# stereo_camera_v2.net
KiCad netlist of a schematic drawn in Altium Designer
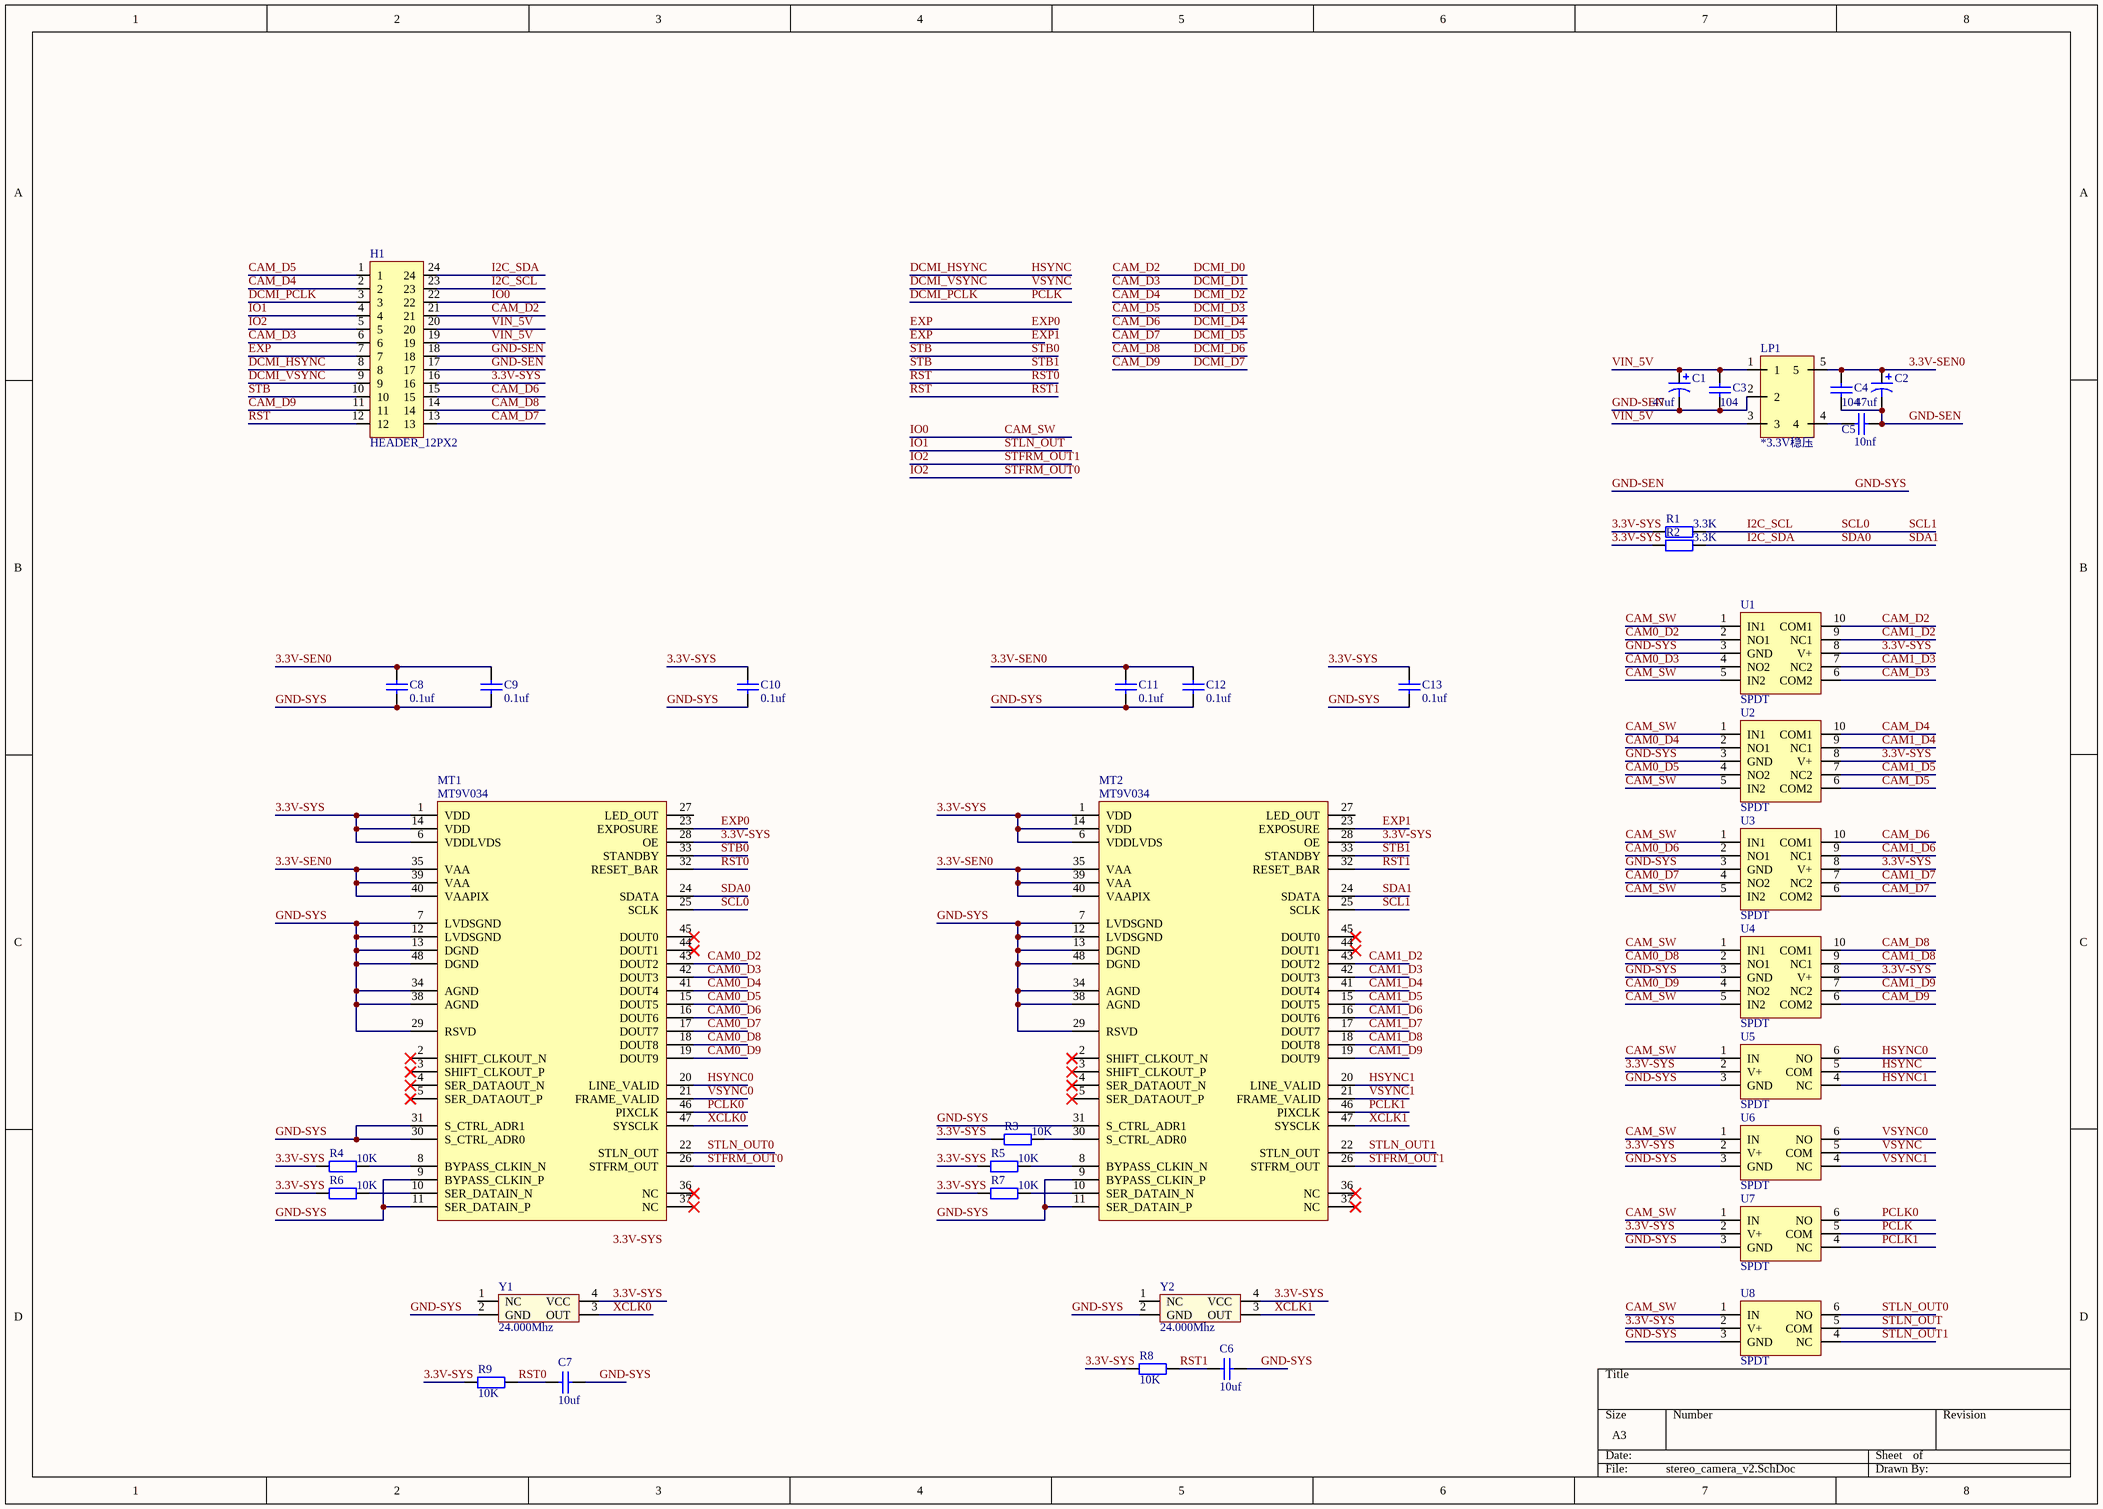
[diagram p0: stereo_camera_v2.SchDoc]

(export (version "E")
  (design (tool "Eeschema 10.0.6"))
  (components
    (comp (ref "C1") (value "47uf") (footprint "MINI-copter:3225_C") (libsource (lib "*") (part "cap_pn")))
    (comp (ref "C2") (value "47uf") (footprint "MINI-copter:3225_C") (libsource (lib "*") (part "cap_pn")))
    (comp (ref "C3")
      (value "104")
      (footprint "H3_Core:C0402")
      (description "Capacitor")
      (fields (field (name "Comment") "Cap") (field (name "PUBLISHER") "Altium Limited"))
      (libsource (lib "Miscellaneous Devices") (part "Cap"))
    )
    (comp (ref "C4")
      (value "104")
      (footprint "H3_Core:C0402")
      (description "Capacitor")
      (fields (field (name "Comment") "Cap") (field (name "PUBLISHER") "Altium Limited"))
      (libsource (lib "Miscellaneous Devices") (part "Cap"))
    )
    (comp (ref "C5")
      (value "10nf")
      (footprint "H3_Core:C0402")
      (description "Capacitor")
      (fields (field (name "Comment") "Cap") (field (name "PUBLISHER") "Altium Limited"))
      (libsource (lib "Miscellaneous Devices") (part "Cap"))
    )
    (comp (ref "C6") (value "10uf") (footprint "H3_Core:C0402") (libsource (lib "*") (part "CAP")))
    (comp (ref "C7") (value "10uf") (footprint "H3_Core:C0402") (libsource (lib "*") (part "CAP")))
    (comp (ref "C8") (value "0.1uf") (footprint "H3_Core:C0402") (libsource (lib "*") (part "CAP")))
    (comp (ref "C9") (value "0.1uf") (footprint "H3_Core:C0402") (libsource (lib "*") (part "CAP")))
    (comp (ref "C10") (value "0.1uf") (footprint "H3_Core:C0402") (libsource (lib "*") (part "CAP")))
    (comp (ref "C11") (value "0.1uf") (footprint "H3_Core:C0402") (libsource (lib "*") (part "CAP")))
    (comp (ref "C12") (value "0.1uf") (footprint "H3_Core:C0402") (libsource (lib "*") (part "CAP")))
    (comp (ref "C13") (value "0.1uf") (footprint "H3_Core:C0402") (libsource (lib "*") (part "CAP")))
    (comp (ref "H1")
      (value "HEADER_12PX2")
      (footprint "连接器:松下AXE-24PIN-0.4mm-header")
      (libsource (lib "MINI-copter") (part "HEADER_12PX2"))
    )
    (comp (ref "LP1")
      (value "*3.3V稳压")
      (footprint "MINI-copter:SOT23-5")
      (libsource (lib "Mini飞控") (part "LP2985"))
    )
    (comp (ref "MT1")
      (value "MT9V034")
      (footprint "CLCC_48")
      (description "CMOS")
      (fields (field (name "PARTNUMBER") "MT9V034C12STM-DP1"))
      (libsource (lib "Schlib1") (part "MT9V034"))
    )
    (comp (ref "MT2")
      (value "MT9V034")
      (footprint "CLCC_48")
      (description "CMOS")
      (fields (field (name "PARTNUMBER") "MT9V034C12STM-DP1"))
      (libsource (lib "Schlib1") (part "MT9V034"))
    )
    (comp (ref "R1")
      (value "3.3K")
      (footprint "H3_Core:R0402")
      (description "Resistor")
      (fields (field (name "Comment") "Res2") (field (name "PUBLISHER") "Altium Limited"))
      (libsource (lib "Miscellaneous Devices") (part "Res2"))
    )
    (comp (ref "R2")
      (value "3.3K")
      (footprint "H3_Core:R0402")
      (description "Resistor")
      (fields (field (name "Comment") "Res2") (field (name "PUBLISHER") "Altium Limited"))
      (libsource (lib "Miscellaneous Devices") (part "Res2"))
    )
    (comp (ref "R3")
      (value "10K")
      (footprint "H3_Core:R0402")
      (description "Resistor")
      (fields (field (name "Comment") "Res2") (field (name "PUBLISHER") "Altium Limited"))
      (libsource (lib "Miscellaneous Devices") (part "Res2"))
    )
    (comp (ref "R4")
      (value "10K")
      (footprint "H3_Core:R0402")
      (description "Resistor")
      (fields (field (name "Comment") "Res2") (field (name "PUBLISHER") "Altium Limited"))
      (libsource (lib "Miscellaneous Devices") (part "Res2"))
    )
    (comp (ref "R5")
      (value "10K")
      (footprint "H3_Core:R0402")
      (description "Resistor")
      (fields (field (name "Comment") "Res2") (field (name "PUBLISHER") "Altium Limited"))
      (libsource (lib "Miscellaneous Devices") (part "Res2"))
    )
    (comp (ref "R6")
      (value "10K")
      (footprint "H3_Core:R0402")
      (description "Resistor")
      (fields (field (name "Comment") "Res2") (field (name "PUBLISHER") "Altium Limited"))
      (libsource (lib "Miscellaneous Devices") (part "Res2"))
    )
    (comp (ref "R7")
      (value "10K")
      (footprint "H3_Core:R0402")
      (description "Resistor")
      (fields (field (name "Comment") "Res2") (field (name "PUBLISHER") "Altium Limited"))
      (libsource (lib "Miscellaneous Devices") (part "Res2"))
    )
    (comp (ref "R8") (value "10K") (footprint "H3_Core:R0402") (libsource (lib "*") (part "RES")))
    (comp (ref "R9") (value "10K") (footprint "H3_Core:R0402") (libsource (lib "*") (part "RES")))
    (comp (ref "U1")
      (value "SPDT")
      (footprint "MINI-copter:MSOP-10")
      (description "analog switch")
      (libsource (lib "MINI-copter") (part "sgm3002"))
    )
    (comp (ref "U2")
      (value "SPDT")
      (footprint "MINI-copter:MSOP-10")
      (description "analog switch")
      (libsource (lib "MINI-copter") (part "sgm3002"))
    )
    (comp (ref "U3")
      (value "SPDT")
      (footprint "MINI-copter:MSOP-10")
      (description "analog switch")
      (libsource (lib "MINI-copter") (part "sgm3002"))
    )
    (comp (ref "U4")
      (value "SPDT")
      (footprint "MINI-copter:MSOP-10")
      (description "analog switch")
      (libsource (lib "MINI-copter") (part "sgm3002"))
    )
    (comp (ref "U5")
      (value "SPDT")
      (footprint "MINI-copter:SC70-6")
      (description "analog switch")
      (libsource (lib "MINI-copter") (part "sgm3001"))
    )
    (comp (ref "U6")
      (value "SPDT")
      (footprint "MINI-copter:SC70-6")
      (description "analog switch")
      (libsource (lib "MINI-copter") (part "sgm3001"))
    )
    (comp (ref "U7")
      (value "SPDT")
      (footprint "MINI-copter:SC70-6")
      (description "analog switch")
      (libsource (lib "MINI-copter") (part "sgm3001"))
    )
    (comp (ref "U8")
      (value "SPDT")
      (footprint "MINI-copter:SC70-6")
      (description "analog switch")
      (libsource (lib "MINI-copter") (part "sgm3001"))
    )
    (comp (ref "Y1")
      (value "24.000Mhz")
      (footprint "MINI-copter:X3225")
      (description "有源晶振")
      (libsource (lib "ATK-2014-09-12") (part "XTAL_S"))
    )
    (comp (ref "Y2")
      (value "24.000Mhz")
      (footprint "MINI-copter:X3225")
      (description "有源晶振")
      (libsource (lib "ATK-2014-09-12") (part "XTAL_S"))
    )
  )
  (nets
    (net (code "1") (name "/3.3V-SEN0") (class "Default")
      (node (ref "C11") (pin "1") (pinfunction "1_1") (pintype "passive"))
      (node (ref "C12") (pin "1") (pinfunction "1_1") (pintype "passive"))
      (node (ref "C2") (pin "1") (pinfunction "1_1") (pintype "passive"))
      (node (ref "C4") (pin "1") (pinfunction "1_1") (pintype "passive"))
      (node (ref "C8") (pin "1") (pinfunction "1_1") (pintype "passive"))
      (node (ref "C9") (pin "1") (pinfunction "1_1") (pintype "passive"))
      (node (ref "LP1") (pin "5") (pinfunction "5_5") (pintype "passive"))
      (node (ref "MT1") (pin "35") (pinfunction "VAA_35") (pintype "passive"))
      (node (ref "MT1") (pin "39") (pinfunction "VAA_39") (pintype "passive"))
      (node (ref "MT1") (pin "40") (pinfunction "VAAPIX_40") (pintype "passive"))
      (node (ref "MT2") (pin "35") (pinfunction "VAA_35") (pintype "passive"))
      (node (ref "MT2") (pin "39") (pinfunction "VAA_39") (pintype "passive"))
      (node (ref "MT2") (pin "40") (pinfunction "VAAPIX_40") (pintype "passive"))
    )
    (net (code "2") (name "/3.3V-SYS") (class "Default")
      (node (ref "C10") (pin "1") (pinfunction "1_1") (pintype "passive"))
      (node (ref "C13") (pin "1") (pinfunction "1_1") (pintype "passive"))
      (node (ref "H1") (pin "16") (pinfunction "16_16") (pintype "passive"))
      (node (ref "MT1") (pin "1") (pinfunction "VDD_1") (pintype "passive"))
      (node (ref "MT1") (pin "14") (pinfunction "VDD_14") (pintype "passive"))
      (node (ref "MT1") (pin "28") (pinfunction "OE_28") (pintype "passive"))
      (node (ref "MT1") (pin "6") (pinfunction "VDDLVDS_6") (pintype "passive"))
      (node (ref "MT2") (pin "1") (pinfunction "VDD_1") (pintype "passive"))
      (node (ref "MT2") (pin "14") (pinfunction "VDD_14") (pintype "passive"))
      (node (ref "MT2") (pin "28") (pinfunction "OE_28") (pintype "passive"))
      (node (ref "MT2") (pin "6") (pinfunction "VDDLVDS_6") (pintype "passive"))
      (node (ref "R1") (pin "2") (pinfunction "2_2") (pintype "passive"))
      (node (ref "R2") (pin "2") (pinfunction "2_2") (pintype "passive"))
      (node (ref "R3") (pin "2") (pinfunction "2_2") (pintype "passive"))
      (node (ref "R4") (pin "2") (pinfunction "2_2") (pintype "passive"))
      (node (ref "R5") (pin "2") (pinfunction "2_2") (pintype "passive"))
      (node (ref "R6") (pin "2") (pinfunction "2_2") (pintype "passive"))
      (node (ref "R7") (pin "2") (pinfunction "2_2") (pintype "passive"))
      (node (ref "R8") (pin "1") (pinfunction "1_1") (pintype "passive"))
      (node (ref "R9") (pin "1") (pinfunction "1_1") (pintype "passive"))
      (node (ref "U1") (pin "8") (pinfunction "V+_8") (pintype "passive"))
      (node (ref "U2") (pin "8") (pinfunction "V+_8") (pintype "passive"))
      (node (ref "U3") (pin "8") (pinfunction "V+_8") (pintype "passive"))
      (node (ref "U4") (pin "8") (pinfunction "V+_8") (pintype "passive"))
      (node (ref "U5") (pin "2") (pinfunction "V+_2") (pintype "passive"))
      (node (ref "U6") (pin "2") (pinfunction "V+_2") (pintype "passive"))
      (node (ref "U7") (pin "2") (pinfunction "V+_2") (pintype "passive"))
      (node (ref "U8") (pin "2") (pinfunction "V+_2") (pintype "passive"))
      (node (ref "Y1") (pin "4") (pinfunction "VCC_4") (pintype "passive"))
      (node (ref "Y2") (pin "4") (pinfunction "VCC_4") (pintype "passive"))
    )
    (net (code "3") (name "/CAM0_D2") (class "Default")
      (node (ref "MT1") (pin "43") (pinfunction "DOUT2_43") (pintype "passive"))
      (node (ref "U1") (pin "2") (pinfunction "NO1_2") (pintype "passive"))
    )
    (net (code "4") (name "/CAM0_D3") (class "Default")
      (node (ref "MT1") (pin "42") (pinfunction "DOUT3_42") (pintype "passive"))
      (node (ref "U1") (pin "4") (pinfunction "NO2_4") (pintype "passive"))
    )
    (net (code "5") (name "/CAM0_D4") (class "Default")
      (node (ref "MT1") (pin "41") (pinfunction "DOUT4_41") (pintype "passive"))
      (node (ref "U2") (pin "2") (pinfunction "NO1_2") (pintype "passive"))
    )
    (net (code "6") (name "/CAM0_D5") (class "Default")
      (node (ref "MT1") (pin "15") (pinfunction "DOUT5_15") (pintype "passive"))
      (node (ref "U2") (pin "4") (pinfunction "NO2_4") (pintype "passive"))
    )
    (net (code "7") (name "/CAM0_D6") (class "Default")
      (node (ref "MT1") (pin "16") (pinfunction "DOUT6_16") (pintype "passive"))
      (node (ref "U3") (pin "2") (pinfunction "NO1_2") (pintype "passive"))
    )
    (net (code "8") (name "/CAM0_D7") (class "Default")
      (node (ref "MT1") (pin "17") (pinfunction "DOUT7_17") (pintype "passive"))
      (node (ref "U3") (pin "4") (pinfunction "NO2_4") (pintype "passive"))
    )
    (net (code "9") (name "/CAM0_D8") (class "Default")
      (node (ref "MT1") (pin "18") (pinfunction "DOUT8_18") (pintype "passive"))
      (node (ref "U4") (pin "2") (pinfunction "NO1_2") (pintype "passive"))
    )
    (net (code "10") (name "/CAM0_D9") (class "Default")
      (node (ref "MT1") (pin "19") (pinfunction "DOUT9_19") (pintype "passive"))
      (node (ref "U4") (pin "4") (pinfunction "NO2_4") (pintype "passive"))
    )
    (net (code "11") (name "/CAM1_D2") (class "Default")
      (node (ref "MT2") (pin "43") (pinfunction "DOUT2_43") (pintype "passive"))
      (node (ref "U1") (pin "9") (pinfunction "NC1_9") (pintype "passive"))
    )
    (net (code "12") (name "/CAM1_D3") (class "Default")
      (node (ref "MT2") (pin "42") (pinfunction "DOUT3_42") (pintype "passive"))
      (node (ref "U1") (pin "7") (pinfunction "NC2_7") (pintype "passive"))
    )
    (net (code "13") (name "/CAM1_D4") (class "Default")
      (node (ref "MT2") (pin "41") (pinfunction "DOUT4_41") (pintype "passive"))
      (node (ref "U2") (pin "9") (pinfunction "NC1_9") (pintype "passive"))
    )
    (net (code "14") (name "/CAM1_D5") (class "Default")
      (node (ref "MT2") (pin "15") (pinfunction "DOUT5_15") (pintype "passive"))
      (node (ref "U2") (pin "7") (pinfunction "NC2_7") (pintype "passive"))
    )
    (net (code "15") (name "/CAM1_D6") (class "Default")
      (node (ref "MT2") (pin "16") (pinfunction "DOUT6_16") (pintype "passive"))
      (node (ref "U3") (pin "9") (pinfunction "NC1_9") (pintype "passive"))
    )
    (net (code "16") (name "/CAM1_D7") (class "Default")
      (node (ref "MT2") (pin "17") (pinfunction "DOUT7_17") (pintype "passive"))
      (node (ref "U3") (pin "7") (pinfunction "NC2_7") (pintype "passive"))
    )
    (net (code "17") (name "/CAM1_D8") (class "Default")
      (node (ref "MT2") (pin "18") (pinfunction "DOUT8_18") (pintype "passive"))
      (node (ref "U4") (pin "9") (pinfunction "NC1_9") (pintype "passive"))
    )
    (net (code "18") (name "/CAM1_D9") (class "Default")
      (node (ref "MT2") (pin "19") (pinfunction "DOUT9_19") (pintype "passive"))
      (node (ref "U4") (pin "7") (pinfunction "NC2_7") (pintype "passive"))
    )
    (net (code "19") (name "/CAM_D2") (class "Default")
      (node (ref "H1") (pin "21") (pinfunction "21_21") (pintype "passive"))
      (node (ref "U1") (pin "10") (pinfunction "COM1_10") (pintype "passive"))
    )
    (net (code "20") (name "/CAM_D3") (class "Default")
      (node (ref "H1") (pin "6") (pinfunction "6_6") (pintype "passive"))
      (node (ref "U1") (pin "6") (pinfunction "COM2_6") (pintype "passive"))
    )
    (net (code "21") (name "/CAM_D4") (class "Default")
      (node (ref "H1") (pin "2") (pinfunction "2_2") (pintype "passive"))
      (node (ref "U2") (pin "10") (pinfunction "COM1_10") (pintype "passive"))
    )
    (net (code "22") (name "/CAM_D5") (class "Default")
      (node (ref "H1") (pin "1") (pinfunction "1_1") (pintype "passive"))
      (node (ref "U2") (pin "6") (pinfunction "COM2_6") (pintype "passive"))
    )
    (net (code "23") (name "/CAM_D6") (class "Default")
      (node (ref "H1") (pin "15") (pinfunction "15_15") (pintype "passive"))
      (node (ref "U3") (pin "10") (pinfunction "COM1_10") (pintype "passive"))
    )
    (net (code "24") (name "/CAM_D7") (class "Default")
      (node (ref "H1") (pin "13") (pinfunction "13_13") (pintype "passive"))
      (node (ref "U3") (pin "6") (pinfunction "COM2_6") (pintype "passive"))
    )
    (net (code "25") (name "/CAM_D8") (class "Default")
      (node (ref "H1") (pin "14") (pinfunction "14_14") (pintype "passive"))
      (node (ref "U4") (pin "10") (pinfunction "COM1_10") (pintype "passive"))
    )
    (net (code "26") (name "/CAM_D9") (class "Default")
      (node (ref "H1") (pin "11") (pinfunction "11_11") (pintype "passive"))
      (node (ref "U4") (pin "6") (pinfunction "COM2_6") (pintype "passive"))
    )
    (net (code "27") (name "/CAM_SW") (class "Default")
      (node (ref "H1") (pin "22") (pinfunction "22_22") (pintype "passive"))
      (node (ref "U1") (pin "1") (pinfunction "IN1_1") (pintype "passive"))
      (node (ref "U1") (pin "5") (pinfunction "IN2_5") (pintype "passive"))
      (node (ref "U2") (pin "1") (pinfunction "IN1_1") (pintype "passive"))
      (node (ref "U2") (pin "5") (pinfunction "IN2_5") (pintype "passive"))
      (node (ref "U3") (pin "1") (pinfunction "IN1_1") (pintype "passive"))
      (node (ref "U3") (pin "5") (pinfunction "IN2_5") (pintype "passive"))
      (node (ref "U4") (pin "1") (pinfunction "IN1_1") (pintype "passive"))
      (node (ref "U4") (pin "5") (pinfunction "IN2_5") (pintype "passive"))
      (node (ref "U5") (pin "1") (pinfunction "IN_1") (pintype "passive"))
      (node (ref "U6") (pin "1") (pinfunction "IN_1") (pintype "passive"))
      (node (ref "U7") (pin "1") (pinfunction "IN_1") (pintype "passive"))
      (node (ref "U8") (pin "1") (pinfunction "IN_1") (pintype "passive"))
    )
    (net (code "28") (name "/DCMI_HSYNC") (class "Default")
      (node (ref "H1") (pin "8") (pinfunction "8_8") (pintype "passive"))
      (node (ref "U5") (pin "5") (pinfunction "COM_5") (pintype "passive"))
    )
    (net (code "29") (name "/DCMI_PCLK") (class "Default")
      (node (ref "H1") (pin "3") (pinfunction "3_3") (pintype "passive"))
      (node (ref "U7") (pin "5") (pinfunction "COM_5") (pintype "passive"))
    )
    (net (code "30") (name "/DCMI_VSYNC") (class "Default")
      (node (ref "H1") (pin "9") (pinfunction "9_9") (pintype "passive"))
      (node (ref "U6") (pin "5") (pinfunction "COM_5") (pintype "passive"))
    )
    (net (code "31") (name "/EXP") (class "Default")
      (node (ref "H1") (pin "7") (pinfunction "7_7") (pintype "passive"))
      (node (ref "MT1") (pin "23") (pinfunction "EXPOSURE_23") (pintype "passive"))
      (node (ref "MT2") (pin "23") (pinfunction "EXPOSURE_23") (pintype "passive"))
    )
    (net (code "32") (name "/GND-SEN") (class "Default")
      (node (ref "C1") (pin "2") (pinfunction "2_2") (pintype "passive"))
      (node (ref "C10") (pin "2") (pinfunction "2_2") (pintype "passive"))
      (node (ref "C11") (pin "2") (pinfunction "2_2") (pintype "passive"))
      (node (ref "C12") (pin "2") (pinfunction "2_2") (pintype "passive"))
      (node (ref "C13") (pin "2") (pinfunction "2_2") (pintype "passive"))
      (node (ref "C2") (pin "2") (pinfunction "2_2") (pintype "passive"))
      (node (ref "C3") (pin "1") (pinfunction "1_1") (pintype "passive"))
      (node (ref "C4") (pin "2") (pinfunction "2_2") (pintype "passive"))
      (node (ref "C5") (pin "1") (pinfunction "1_1") (pintype "passive"))
      (node (ref "C6") (pin "1") (pinfunction "1_1") (pintype "passive"))
      (node (ref "C7") (pin "2") (pinfunction "2_2") (pintype "passive"))
      (node (ref "C8") (pin "2") (pinfunction "2_2") (pintype "passive"))
      (node (ref "C9") (pin "2") (pinfunction "2_2") (pintype "passive"))
      (node (ref "H1") (pin "17") (pinfunction "17_17") (pintype "passive"))
      (node (ref "H1") (pin "18") (pinfunction "18_18") (pintype "passive"))
      (node (ref "LP1") (pin "2") (pinfunction "2_2") (pintype "passive"))
      (node (ref "MT1") (pin "11") (pinfunction "SER_DATAIN_P_11") (pintype "passive"))
      (node (ref "MT1") (pin "12") (pinfunction "LVDSGND_12") (pintype "passive"))
      (node (ref "MT1") (pin "13") (pinfunction "DGND_13") (pintype "passive"))
      (node (ref "MT1") (pin "29") (pinfunction "RSVD_29") (pintype "passive"))
      (node (ref "MT1") (pin "30") (pinfunction "S_CTRL_ADR0_30") (pintype "passive"))
      (node (ref "MT1") (pin "31") (pinfunction "S_CTRL_ADR1_31") (pintype "passive"))
      (node (ref "MT1") (pin "34") (pinfunction "AGND_34") (pintype "passive"))
      (node (ref "MT1") (pin "38") (pinfunction "AGND_38") (pintype "passive"))
      (node (ref "MT1") (pin "48") (pinfunction "DGND_48") (pintype "passive"))
      (node (ref "MT1") (pin "7") (pinfunction "LVDSGND_7") (pintype "passive"))
      (node (ref "MT1") (pin "9") (pinfunction "BYPASS_CLKIN_P_9") (pintype "passive"))
      (node (ref "MT2") (pin "11") (pinfunction "SER_DATAIN_P_11") (pintype "passive"))
      (node (ref "MT2") (pin "12") (pinfunction "LVDSGND_12") (pintype "passive"))
      (node (ref "MT2") (pin "13") (pinfunction "DGND_13") (pintype "passive"))
      (node (ref "MT2") (pin "29") (pinfunction "RSVD_29") (pintype "passive"))
      (node (ref "MT2") (pin "31") (pinfunction "S_CTRL_ADR1_31") (pintype "passive"))
      (node (ref "MT2") (pin "34") (pinfunction "AGND_34") (pintype "passive"))
      (node (ref "MT2") (pin "38") (pinfunction "AGND_38") (pintype "passive"))
      (node (ref "MT2") (pin "48") (pinfunction "DGND_48") (pintype "passive"))
      (node (ref "MT2") (pin "7") (pinfunction "LVDSGND_7") (pintype "passive"))
      (node (ref "MT2") (pin "9") (pinfunction "BYPASS_CLKIN_P_9") (pintype "passive"))
      (node (ref "U1") (pin "3") (pinfunction "GND_3") (pintype "passive"))
      (node (ref "U2") (pin "3") (pinfunction "GND_3") (pintype "passive"))
      (node (ref "U3") (pin "3") (pinfunction "GND_3") (pintype "passive"))
      (node (ref "U4") (pin "3") (pinfunction "GND_3") (pintype "passive"))
      (node (ref "U5") (pin "3") (pinfunction "GND_3") (pintype "passive"))
      (node (ref "U6") (pin "3") (pinfunction "GND_3") (pintype "passive"))
      (node (ref "U7") (pin "3") (pinfunction "GND_3") (pintype "passive"))
      (node (ref "U8") (pin "3") (pinfunction "GND_3") (pintype "passive"))
      (node (ref "Y1") (pin "2") (pinfunction "GND_2") (pintype "passive"))
      (node (ref "Y2") (pin "2") (pinfunction "GND_2") (pintype "passive"))
    )
    (net (code "33") (name "/HSYNC0") (class "Default")
      (node (ref "MT1") (pin "20") (pinfunction "LINE_VALID_20") (pintype "passive"))
      (node (ref "U5") (pin "6") (pinfunction "NO_6") (pintype "passive"))
    )
    (net (code "34") (name "/HSYNC1") (class "Default")
      (node (ref "MT2") (pin "20") (pinfunction "LINE_VALID_20") (pintype "passive"))
      (node (ref "U5") (pin "4") (pinfunction "NC_4") (pintype "passive"))
    )
    (net (code "35") (name "/I2C_SCL") (class "Default")
      (node (ref "H1") (pin "23") (pinfunction "23_23") (pintype "passive"))
      (node (ref "MT1") (pin "25") (pinfunction "SCLK_25") (pintype "passive"))
      (node (ref "MT2") (pin "25") (pinfunction "SCLK_25") (pintype "passive"))
      (node (ref "R1") (pin "1") (pinfunction "1_1") (pintype "passive"))
    )
    (net (code "36") (name "/I2C_SDA") (class "Default")
      (node (ref "H1") (pin "24") (pinfunction "24_24") (pintype "passive"))
      (node (ref "MT1") (pin "24") (pinfunction "SDATA_24") (pintype "passive"))
      (node (ref "MT2") (pin "24") (pinfunction "SDATA_24") (pintype "passive"))
      (node (ref "R2") (pin "1") (pinfunction "1_1") (pintype "passive"))
    )
    (net (code "37") (name "/IO1") (class "Default")
      (node (ref "H1") (pin "4") (pinfunction "4_4") (pintype "passive"))
      (node (ref "U8") (pin "5") (pinfunction "COM_5") (pintype "passive"))
    )
    (net (code "38") (name "/IO2") (class "Default")
      (node (ref "H1") (pin "5") (pinfunction "5_5") (pintype "passive"))
      (node (ref "MT1") (pin "26") (pinfunction "STFRM_OUT_26") (pintype "passive"))
      (node (ref "MT2") (pin "26") (pinfunction "STFRM_OUT_26") (pintype "passive"))
    )
    (net (code "39") (name "/PCLK0") (class "Default")
      (node (ref "MT1") (pin "46") (pinfunction "PIXCLK_46") (pintype "passive"))
      (node (ref "U7") (pin "6") (pinfunction "NO_6") (pintype "passive"))
    )
    (net (code "40") (name "/PCLK1") (class "Default")
      (node (ref "MT2") (pin "46") (pinfunction "PIXCLK_46") (pintype "passive"))
      (node (ref "U7") (pin "4") (pinfunction "NC_4") (pintype "passive"))
    )
    (net (code "41") (name "/RST") (class "Default")
      (node (ref "C6") (pin "2") (pinfunction "2_2") (pintype "passive"))
      (node (ref "C7") (pin "1") (pinfunction "1_1") (pintype "passive"))
      (node (ref "H1") (pin "12") (pinfunction "12_12") (pintype "passive"))
      (node (ref "MT1") (pin "32") (pinfunction "RESET_BAR_32") (pintype "passive"))
      (node (ref "MT2") (pin "32") (pinfunction "RESET_BAR_32") (pintype "passive"))
      (node (ref "R8") (pin "2") (pinfunction "2_2") (pintype "passive"))
      (node (ref "R9") (pin "2") (pinfunction "2_2") (pintype "passive"))
    )
    (net (code "42") (name "/STB") (class "Default")
      (node (ref "H1") (pin "10") (pinfunction "10_10") (pintype "passive"))
      (node (ref "MT1") (pin "33") (pinfunction "STANDBY_33") (pintype "passive"))
      (node (ref "MT2") (pin "33") (pinfunction "STANDBY_33") (pintype "passive"))
    )
    (net (code "43") (name "/STLN_OUT0") (class "Default")
      (node (ref "MT1") (pin "22") (pinfunction "STLN_OUT_22") (pintype "passive"))
      (node (ref "U8") (pin "6") (pinfunction "NO_6") (pintype "passive"))
    )
    (net (code "44") (name "/STLN_OUT1") (class "Default")
      (node (ref "MT2") (pin "22") (pinfunction "STLN_OUT_22") (pintype "passive"))
      (node (ref "U8") (pin "4") (pinfunction "NC_4") (pintype "passive"))
    )
    (net (code "45") (name "/VIN_5V") (class "Default")
      (node (ref "C1") (pin "1") (pinfunction "1_1") (pintype "passive"))
      (node (ref "C3") (pin "2") (pinfunction "2_2") (pintype "passive"))
      (node (ref "H1") (pin "19") (pinfunction "19_19") (pintype "passive"))
      (node (ref "H1") (pin "20") (pinfunction "20_20") (pintype "passive"))
      (node (ref "LP1") (pin "1") (pinfunction "1_1") (pintype "passive"))
      (node (ref "LP1") (pin "3") (pinfunction "3_3") (pintype "passive"))
    )
    (net (code "46") (name "/VSYNC0") (class "Default")
      (node (ref "MT1") (pin "21") (pinfunction "FRAME_VALID_21") (pintype "passive"))
      (node (ref "U6") (pin "6") (pinfunction "NO_6") (pintype "passive"))
    )
    (net (code "47") (name "/VSYNC1") (class "Default")
      (node (ref "MT2") (pin "21") (pinfunction "FRAME_VALID_21") (pintype "passive"))
      (node (ref "U6") (pin "4") (pinfunction "NC_4") (pintype "passive"))
    )
    (net (code "48") (name "/XCLK0") (class "Default")
      (node (ref "MT1") (pin "47") (pinfunction "SYSCLK_47") (pintype "passive"))
      (node (ref "Y1") (pin "3") (pinfunction "OUT_3") (pintype "passive"))
    )
    (net (code "49") (name "/XCLK1") (class "Default")
      (node (ref "MT2") (pin "47") (pinfunction "SYSCLK_47") (pintype "passive"))
      (node (ref "Y2") (pin "3") (pinfunction "OUT_3") (pintype "passive"))
    )
    (net (code "50") (name "Net-(C5-Pad2)") (class "Default")
      (node (ref "C5") (pin "2") (pinfunction "2_2") (pintype "passive"))
      (node (ref "LP1") (pin "4") (pinfunction "4_4") (pintype "passive"))
    )
    (net (code "51") (name "Net-(MT1-BYPASS_CLKIN_N)") (class "Default")
      (node (ref "MT1") (pin "8") (pinfunction "BYPASS_CLKIN_N_8") (pintype "passive"))
      (node (ref "R4") (pin "1") (pinfunction "1_1") (pintype "passive"))
    )
    (net (code "52") (name "Net-(MT1-SER_DATAIN_N)") (class "Default")
      (node (ref "MT1") (pin "10") (pinfunction "SER_DATAIN_N_10") (pintype "passive"))
      (node (ref "R6") (pin "1") (pinfunction "1_1") (pintype "passive"))
    )
    (net (code "53") (name "Net-(MT2-BYPASS_CLKIN_N)") (class "Default")
      (node (ref "MT2") (pin "8") (pinfunction "BYPASS_CLKIN_N_8") (pintype "passive"))
      (node (ref "R5") (pin "1") (pinfunction "1_1") (pintype "passive"))
    )
    (net (code "54") (name "Net-(MT2-SER_DATAIN_N)") (class "Default")
      (node (ref "MT2") (pin "10") (pinfunction "SER_DATAIN_N_10") (pintype "passive"))
      (node (ref "R7") (pin "1") (pinfunction "1_1") (pintype "passive"))
    )
    (net (code "55") (name "Net-(MT2-S_CTRL_ADR0)") (class "Default")
      (node (ref "MT2") (pin "30") (pinfunction "S_CTRL_ADR0_30") (pintype "passive"))
      (node (ref "R3") (pin "1") (pinfunction "1_1") (pintype "passive"))
    )
    (net (code "56") (name "unconnected-(MT1-DOUT0-Pad45)") (class "Default")
      (node (ref "MT1") (pin "45") (pinfunction "DOUT0_45") (pintype "passive+no_connect"))
    )
    (net (code "57") (name "unconnected-(MT1-DOUT1-Pad44)") (class "Default")
      (node (ref "MT1") (pin "44") (pinfunction "DOUT1_44") (pintype "passive+no_connect"))
    )
    (net (code "58") (name "unconnected-(MT1-LED_OUT-Pad27)") (class "Default")
      (node (ref "MT1") (pin "27") (pinfunction "LED_OUT_27") (pintype "passive"))
    )
    (net (code "59") (name "unconnected-(MT1-NC-Pad36)") (class "Default")
      (node (ref "MT1") (pin "36") (pinfunction "NC_36") (pintype "passive+no_connect"))
    )
    (net (code "60") (name "unconnected-(MT1-NC-Pad37)") (class "Default")
      (node (ref "MT1") (pin "37") (pinfunction "NC_37") (pintype "passive+no_connect"))
    )
    (net (code "61") (name "unconnected-(MT1-SER_DATAOUT_N-Pad4)") (class "Default")
      (node (ref "MT1") (pin "4") (pinfunction "SER_DATAOUT_N_4") (pintype "passive+no_connect"))
    )
    (net (code "62") (name "unconnected-(MT1-SER_DATAOUT_P-Pad5)") (class "Default")
      (node (ref "MT1") (pin "5") (pinfunction "SER_DATAOUT_P_5") (pintype "passive+no_connect"))
    )
    (net (code "63") (name "unconnected-(MT1-SHIFT_CLKOUT_N-Pad2)") (class "Default")
      (node (ref "MT1") (pin "2") (pinfunction "SHIFT_CLKOUT_N_2") (pintype "passive+no_connect"))
    )
    (net (code "64") (name "unconnected-(MT1-SHIFT_CLKOUT_P-Pad3)") (class "Default")
      (node (ref "MT1") (pin "3") (pinfunction "SHIFT_CLKOUT_P_3") (pintype "passive+no_connect"))
    )
    (net (code "65") (name "unconnected-(MT2-DOUT0-Pad45)") (class "Default")
      (node (ref "MT2") (pin "45") (pinfunction "DOUT0_45") (pintype "passive+no_connect"))
    )
    (net (code "66") (name "unconnected-(MT2-DOUT1-Pad44)") (class "Default")
      (node (ref "MT2") (pin "44") (pinfunction "DOUT1_44") (pintype "passive+no_connect"))
    )
    (net (code "67") (name "unconnected-(MT2-LED_OUT-Pad27)") (class "Default")
      (node (ref "MT2") (pin "27") (pinfunction "LED_OUT_27") (pintype "passive"))
    )
    (net (code "68") (name "unconnected-(MT2-NC-Pad36)") (class "Default")
      (node (ref "MT2") (pin "36") (pinfunction "NC_36") (pintype "passive+no_connect"))
    )
    (net (code "69") (name "unconnected-(MT2-NC-Pad37)") (class "Default")
      (node (ref "MT2") (pin "37") (pinfunction "NC_37") (pintype "passive+no_connect"))
    )
    (net (code "70") (name "unconnected-(MT2-SER_DATAOUT_N-Pad4)") (class "Default")
      (node (ref "MT2") (pin "4") (pinfunction "SER_DATAOUT_N_4") (pintype "passive+no_connect"))
    )
    (net (code "71") (name "unconnected-(MT2-SER_DATAOUT_P-Pad5)") (class "Default")
      (node (ref "MT2") (pin "5") (pinfunction "SER_DATAOUT_P_5") (pintype "passive+no_connect"))
    )
    (net (code "72") (name "unconnected-(MT2-SHIFT_CLKOUT_N-Pad2)") (class "Default")
      (node (ref "MT2") (pin "2") (pinfunction "SHIFT_CLKOUT_N_2") (pintype "passive+no_connect"))
    )
    (net (code "73") (name "unconnected-(MT2-SHIFT_CLKOUT_P-Pad3)") (class "Default")
      (node (ref "MT2") (pin "3") (pinfunction "SHIFT_CLKOUT_P_3") (pintype "passive+no_connect"))
    )
    (net (code "74") (name "unconnected-(Y1-NC-Pad1)") (class "Default")
      (node (ref "Y1") (pin "1") (pinfunction "NC_1") (pintype "passive"))
    )
    (net (code "75") (name "unconnected-(Y2-NC-Pad1)") (class "Default")
      (node (ref "Y2") (pin "1") (pinfunction "NC_1") (pintype "passive"))
    )
  )
)
